# Plasma_Speaker.net
KiCad netlist of a schematic drawn in Altium Designer
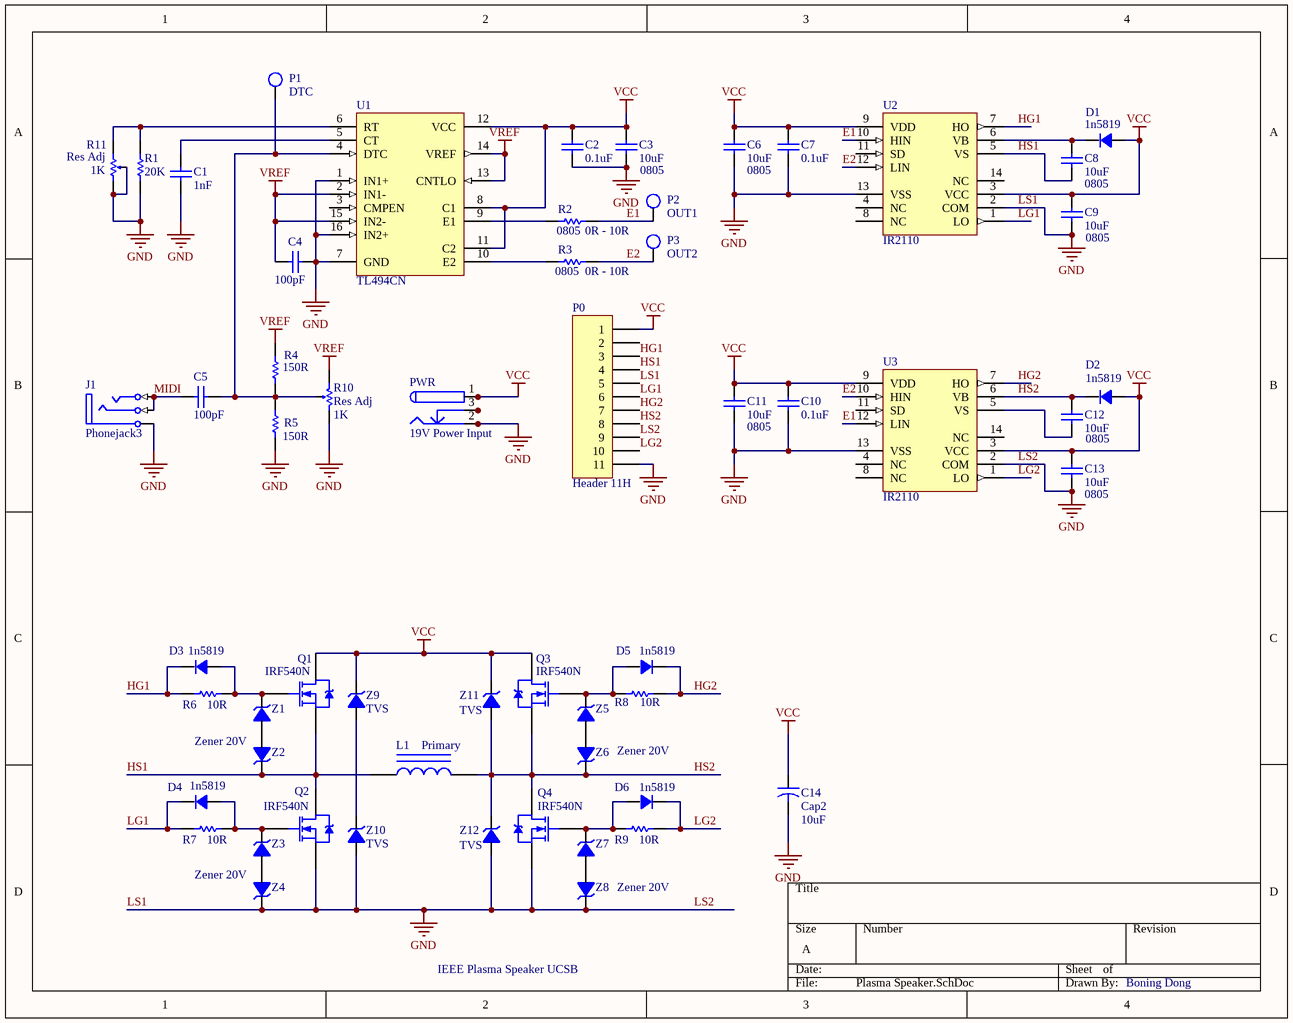
[diagram p0: Plasma Speaker.SchDoc]

(export (version "E")
  (design (tool "Eeschema 10.0.6"))
  (components
    (comp (ref "C1")
      (value "1nF")
      (footprint "RAD-0.3")
      (description "Capacitor")
      (fields (field (name "Comment") "0603") (field (name "PUBLISHER") "Altium Limited"))
      (libsource (lib "Miscellaneous Devices") (part "Cap"))
    )
    (comp (ref "C2")
      (value "0.1uF")
      (footprint "RAD-0.3")
      (description "Capacitor")
      (fields (field (name "Comment") "0603") (field (name "PUBLISHER") "Altium Limited"))
      (libsource (lib "Miscellaneous Devices") (part "Cap"))
    )
    (comp (ref "C3")
      (value "0805")
      (footprint "RAD-0.3")
      (description "Capacitor")
      (fields (field (name "ALTIUM_VALUE") "10uF") (field (name "PUBLISHER") "Altium Limited"))
      (libsource (lib "Miscellaneous Devices") (part "Cap"))
    )
    (comp (ref "C4")
      (value "100pF")
      (footprint "RAD-0.3")
      (description "Capacitor")
      (fields (field (name "Comment") "0603") (field (name "PUBLISHER") "Altium Limited"))
      (libsource (lib "Miscellaneous Devices") (part "Cap"))
    )
    (comp (ref "C5")
      (value "100pF")
      (footprint "RAD-0.3")
      (description "Capacitor")
      (fields (field (name "Comment") "0603") (field (name "PUBLISHER") "Altium Limited"))
      (libsource (lib "Miscellaneous Devices") (part "Cap"))
    )
    (comp (ref "C6")
      (value "0805")
      (footprint "RAD-0.3")
      (description "Capacitor")
      (fields (field (name "ALTIUM_VALUE") "10uF") (field (name "PUBLISHER") "Altium Limited"))
      (libsource (lib "Miscellaneous Devices") (part "Cap"))
    )
    (comp (ref "C7")
      (value "0.1uF")
      (footprint "RAD-0.3")
      (description "Capacitor")
      (fields (field (name "Comment") "0603") (field (name "PUBLISHER") "Altium Limited"))
      (libsource (lib "Miscellaneous Devices") (part "Cap"))
    )
    (comp (ref "C8")
      (value "0805")
      (footprint "RAD-0.3")
      (description "Capacitor")
      (fields (field (name "ALTIUM_VALUE") "10uF") (field (name "PUBLISHER") "Altium Limited"))
      (libsource (lib "Miscellaneous Devices") (part "Cap"))
    )
    (comp (ref "C9")
      (value "0805")
      (footprint "RAD-0.3")
      (description "Capacitor")
      (fields (field (name "ALTIUM_VALUE") "10uF") (field (name "PUBLISHER") "Altium Limited"))
      (libsource (lib "Miscellaneous Devices") (part "Cap"))
    )
    (comp (ref "C10")
      (value "0.1uF")
      (footprint "RAD-0.3")
      (description "Capacitor")
      (fields (field (name "Comment") "0603") (field (name "PUBLISHER") "Altium Limited"))
      (libsource (lib "Miscellaneous Devices") (part "Cap"))
    )
    (comp (ref "C11")
      (value "0805")
      (footprint "RAD-0.3")
      (description "Capacitor")
      (fields (field (name "ALTIUM_VALUE") "10uF") (field (name "PUBLISHER") "Altium Limited"))
      (libsource (lib "Miscellaneous Devices") (part "Cap"))
    )
    (comp (ref "C12")
      (value "0805")
      (footprint "RAD-0.3")
      (description "Capacitor")
      (fields (field (name "ALTIUM_VALUE") "10uF") (field (name "PUBLISHER") "Altium Limited"))
      (libsource (lib "Miscellaneous Devices") (part "Cap"))
    )
    (comp (ref "C13")
      (value "0805")
      (footprint "RAD-0.3")
      (description "Capacitor")
      (fields (field (name "ALTIUM_VALUE") "10uF") (field (name "PUBLISHER") "Altium Limited"))
      (libsource (lib "Miscellaneous Devices") (part "Cap"))
    )
    (comp (ref "C14")
      (value "Cap2")
      (footprint "CAPR5-4X5")
      (description "Capacitor")
      (fields (field (name "ALTIUM_VALUE") "10uF") (field (name "PUBLISHER") "Altium Limited"))
      (libsource (lib "Miscellaneous Devices") (part "Cap2"))
    )
    (comp (ref "D1")
      (value "1n5819")
      (footprint "DIODE-0.7")
      (description "Zener Diode")
      (fields (field (name "PUBLISHER") "Altium Limited"))
      (libsource (lib "Miscellaneous Devices") (part "Diode S"))
    )
    (comp (ref "D2")
      (value "1n5819")
      (footprint "DIODE-0.7")
      (description "Zener Diode")
      (fields (field (name "PUBLISHER") "Altium Limited"))
      (libsource (lib "Miscellaneous Devices") (part "Diode S"))
    )
    (comp (ref "D3")
      (value "1n5819")
      (footprint "DIODE-0.7")
      (description "Zener Diode")
      (fields (field (name "PUBLISHER") "Altium Limited"))
      (libsource (lib "Miscellaneous Devices") (part "Diode S"))
    )
    (comp (ref "D4")
      (value "1n5819")
      (footprint "DIODE-0.7")
      (description "Zener Diode")
      (fields (field (name "PUBLISHER") "Altium Limited"))
      (libsource (lib "Miscellaneous Devices") (part "Diode S"))
    )
    (comp (ref "D5")
      (value "1n5819")
      (footprint "DIODE-0.7")
      (description "Zener Diode")
      (fields (field (name "PUBLISHER") "Altium Limited"))
      (libsource (lib "Miscellaneous Devices") (part "Diode S"))
    )
    (comp (ref "D6")
      (value "1n5819")
      (footprint "DIODE-0.7")
      (description "Zener Diode")
      (fields (field (name "PUBLISHER") "Altium Limited"))
      (libsource (lib "Miscellaneous Devices") (part "Diode S"))
    )
    (comp (ref "J1")
      (value "Phonejack3")
      (footprint "JACK/6-V3")
      (description "Jack Socket, 1/4\" [6.5mm], Thru-Hole, Vertical, 3-Conductor Open Circuit (Non-Normalling)")
      (fields (field (name "PUBLISHER") "Altium Limited"))
      (libsource (lib "Miscellaneous Connectors") (part "Phonejack3"))
    )
    (comp (ref "L1")
      (value "Primary")
      (footprint "AXIAL-0.9")
      (description "Magnetic-Core Inductor")
      (fields (field (name "Comment") "Inductor Iron") (field (name "PUBLISHER") "Altium Limited"))
      (libsource (lib "Miscellaneous Devices") (part "Inductor Iron"))
    )
    (comp (ref "P0")
      (value "Header 11H")
      (footprint "HDR1X11H")
      (description "Header, 11-Pin, Right Angle")
      (fields (field (name "PUBLISHER") "Altium Limited"))
      (libsource (lib "Miscellaneous Connectors") (part "Header 11H"))
    )
    (comp (ref "P1")
      (value "DTC")
      (description "Test Point")
      (libsource (lib "Miscellaneous Connectors") (part "TP"))
    )
    (comp (ref "P2")
      (value "OUT1")
      (description "Test Point")
      (libsource (lib "Miscellaneous Connectors") (part "TP"))
    )
    (comp (ref "P3")
      (value "OUT2")
      (description "Test Point")
      (libsource (lib "Miscellaneous Connectors") (part "TP"))
    )
    (comp (ref "PWR")
      (value "19V Power Input")
      (footprint "KLD-0202")
      (description "Low Voltage Power Supply Connector")
      (fields (field (name "PUBLISHER") "Altium Limited"))
      (libsource (lib "Miscellaneous Connectors") (part "PWR2.5"))
    )
    (comp (ref "Q1")
      (value "IRF540N")
      (footprint "TO-220AB")
      (description "N-Channel Power MOSFET")
      (fields (field (name "PUBLISHER") "Altium Limited"))
      (libsource (lib "Transistor") (part "IRF540N"))
    )
    (comp (ref "Q2")
      (value "IRF540N")
      (footprint "TO-220AB")
      (description "N-Channel Power MOSFET")
      (fields (field (name "PUBLISHER") "Altium Limited"))
      (libsource (lib "Transistor") (part "IRF540N"))
    )
    (comp (ref "Q3")
      (value "IRF540N")
      (footprint "TO-220AB")
      (description "N-Channel Power MOSFET")
      (fields (field (name "PUBLISHER") "Altium Limited"))
      (libsource (lib "Transistor") (part "IRF540N"))
    )
    (comp (ref "Q4")
      (value "IRF540N")
      (footprint "TO-220AB")
      (description "N-Channel Power MOSFET")
      (fields (field (name "PUBLISHER") "Altium Limited"))
      (libsource (lib "Transistor") (part "IRF540N"))
    )
    (comp (ref "R1")
      (value "20K")
      (footprint "AXIAL-0.3")
      (description "Resistor")
      (fields (field (name "Comment") "0603") (field (name "PUBLISHER") "Altium Limited"))
      (libsource (lib "Miscellaneous Devices") (part "Res1"))
    )
    (comp (ref "R2")
      (value "0805")
      (footprint "AXIAL-0.3")
      (description "Resistor")
      (fields (field (name "ALTIUM_VALUE") "0R - 10R") (field (name "PUBLISHER") "Altium Limited"))
      (libsource (lib "Miscellaneous Devices") (part "Res1"))
    )
    (comp (ref "R3")
      (value "0805")
      (footprint "AXIAL-0.3")
      (description "Resistor")
      (fields (field (name "ALTIUM_VALUE") "0R - 10R") (field (name "PUBLISHER") "Altium Limited"))
      (libsource (lib "Miscellaneous Devices") (part "Res1"))
    )
    (comp (ref "R4")
      (value "150R")
      (footprint "AXIAL-0.3")
      (description "Resistor")
      (fields (field (name "Comment") "0603") (field (name "PUBLISHER") "Altium Limited"))
      (libsource (lib "Miscellaneous Devices") (part "Res1"))
    )
    (comp (ref "R5")
      (value "150R")
      (footprint "AXIAL-0.3")
      (description "Resistor")
      (fields (field (name "Comment") "0603") (field (name "PUBLISHER") "Altium Limited"))
      (libsource (lib "Miscellaneous Devices") (part "Res1"))
    )
    (comp (ref "R6")
      (value "10R")
      (footprint "AXIAL-0.3")
      (description "Resistor")
      (fields (field (name "Comment") "0805") (field (name "PUBLISHER") "Altium Limited"))
      (libsource (lib "Miscellaneous Devices") (part "Res1"))
    )
    (comp (ref "R7")
      (value "10R")
      (footprint "AXIAL-0.3")
      (description "Resistor")
      (fields (field (name "Comment") "0805") (field (name "PUBLISHER") "Altium Limited"))
      (libsource (lib "Miscellaneous Devices") (part "Res1"))
    )
    (comp (ref "R8")
      (value "10R")
      (footprint "AXIAL-0.3")
      (description "Resistor")
      (fields (field (name "Comment") "0805") (field (name "PUBLISHER") "Altium Limited"))
      (libsource (lib "Miscellaneous Devices") (part "Res1"))
    )
    (comp (ref "R9")
      (value "10R")
      (footprint "AXIAL-0.3")
      (description "Resistor")
      (fields (field (name "Comment") "0805") (field (name "PUBLISHER") "Altium Limited"))
      (libsource (lib "Miscellaneous Devices") (part "Res1"))
    )
    (comp (ref "R10")
      (value "Res Adj")
      (footprint "AXIAL-0.3")
      (description "Resistor")
      (fields (field (name "ALTIUM_VALUE") "1K") (field (name "PUBLISHER") "Altium Limited"))
      (libsource (lib "Miscellaneous Devices") (part "Res Adj"))
    )
    (comp (ref "R11")
      (value "Res Adj")
      (footprint "AXIAL-0.3")
      (description "Resistor")
      (fields (field (name "ALTIUM_VALUE") "1K") (field (name "PUBLISHER") "Altium Limited"))
      (libsource (lib "Miscellaneous Devices") (part "Res Adj"))
    )
    (comp (ref "U1")
      (value "TL494CN")
      (footprint "648-06")
      (description "Switchmode Pulse Width Modulation Control Circuit")
      (fields (field (name "PUBLISHER") "Altium Limited"))
      (libsource (lib "Motorola Power Mgt SMPS Controller") (part "TL494CN"))
    )
    (comp (ref "U2")
      (value "IR2110")
      (footprint "PDIP14")
      (description "High and Low Side Driver")
      (fields (field (name "PUBLISHER") "Altium Limited"))
      (libsource (lib "IR Interface Bridge Driver") (part "IR2110"))
    )
    (comp (ref "U3")
      (value "IR2110")
      (footprint "PDIP14")
      (description "High and Low Side Driver")
      (fields (field (name "PUBLISHER") "Altium Limited"))
      (libsource (lib "IR Interface Bridge Driver") (part "IR2110"))
    )
    (comp (ref "Z1")
      (value "Zener 20V")
      (footprint "DIODE-0.7")
      (description "Zener Diode")
      (fields (field (name "PUBLISHER") "Altium Limited"))
      (libsource (lib "Miscellaneous Devices") (part "Zener"))
    )
    (comp (ref "Z2")
      (value "Zener")
      (footprint "DIODE-0.7")
      (description "Zener Diode")
      (fields (field (name "PUBLISHER") "Altium Limited"))
      (libsource (lib "Miscellaneous Devices") (part "Zener"))
    )
    (comp (ref "Z3")
      (value "Zener 20V")
      (footprint "DIODE-0.7")
      (description "Zener Diode")
      (fields (field (name "PUBLISHER") "Altium Limited"))
      (libsource (lib "Miscellaneous Devices") (part "Zener"))
    )
    (comp (ref "Z4")
      (value "Zener")
      (footprint "DIODE-0.7")
      (description "Zener Diode")
      (fields (field (name "PUBLISHER") "Altium Limited"))
      (libsource (lib "Miscellaneous Devices") (part "Zener"))
    )
    (comp (ref "Z5")
      (value "Zener 20V")
      (footprint "DIODE-0.7")
      (description "Zener Diode")
      (fields (field (name "PUBLISHER") "Altium Limited"))
      (libsource (lib "Miscellaneous Devices") (part "Zener"))
    )
    (comp (ref "Z6")
      (value "Zener")
      (footprint "DIODE-0.7")
      (description "Zener Diode")
      (fields (field (name "PUBLISHER") "Altium Limited"))
      (libsource (lib "Miscellaneous Devices") (part "Zener"))
    )
    (comp (ref "Z7")
      (value "Zener 20V")
      (footprint "DIODE-0.7")
      (description "Zener Diode")
      (fields (field (name "PUBLISHER") "Altium Limited"))
      (libsource (lib "Miscellaneous Devices") (part "Zener"))
    )
    (comp (ref "Z8")
      (value "Zener")
      (footprint "DIODE-0.7")
      (description "Zener Diode")
      (fields (field (name "PUBLISHER") "Altium Limited"))
      (libsource (lib "Miscellaneous Devices") (part "Zener"))
    )
    (comp (ref "Z9")
      (value "TVS")
      (footprint "DIODE-0.7")
      (description "Zener Diode")
      (fields (field (name "PUBLISHER") "Altium Limited"))
      (libsource (lib "Miscellaneous Devices") (part "Zener"))
    )
    (comp (ref "Z10")
      (value "TVS")
      (footprint "DIODE-0.7")
      (description "Zener Diode")
      (fields (field (name "PUBLISHER") "Altium Limited"))
      (libsource (lib "Miscellaneous Devices") (part "Zener"))
    )
    (comp (ref "Z11")
      (value "TVS")
      (footprint "DIODE-0.7")
      (description "Zener Diode")
      (fields (field (name "PUBLISHER") "Altium Limited"))
      (libsource (lib "Miscellaneous Devices") (part "Zener"))
    )
    (comp (ref "Z12")
      (value "TVS")
      (footprint "DIODE-0.7")
      (description "Zener Diode")
      (fields (field (name "PUBLISHER") "Altium Limited"))
      (libsource (lib "Miscellaneous Devices") (part "Zener"))
    )
  )
  (nets
    (net (code "1") (name "/E1") (class "Default")
      (node (ref "P2") (pin "1") (pinfunction "1_1") (pintype "passive"))
      (node (ref "R2") (pin "1") (pinfunction "1_1") (pintype "passive"))
      (node (ref "U2") (pin "10") (pinfunction "HIN_10") (pintype "input"))
      (node (ref "U3") (pin "12") (pinfunction "LIN_12") (pintype "input"))
    )
    (net (code "2") (name "/E2") (class "Default")
      (node (ref "P3") (pin "1") (pinfunction "1_1") (pintype "passive"))
      (node (ref "R3") (pin "1") (pinfunction "1_1") (pintype "passive"))
      (node (ref "U2") (pin "12") (pinfunction "LIN_12") (pintype "input"))
      (node (ref "U3") (pin "10") (pinfunction "HIN_10") (pintype "input"))
    )
    (net (code "3") (name "/HG1") (class "Default")
      (node (ref "D3") (pin "2") (pinfunction "2_2") (pintype "passive"))
      (node (ref "P0") (pin "3") (pinfunction "3_3") (pintype "passive"))
      (node (ref "R6") (pin "2") (pinfunction "2_2") (pintype "passive"))
      (node (ref "U2") (pin "7") (pinfunction "HO_7") (pintype "output"))
    )
    (net (code "4") (name "/HG2") (class "Default")
      (node (ref "D5") (pin "2") (pinfunction "2_2") (pintype "passive"))
      (node (ref "P0") (pin "7") (pinfunction "7_7") (pintype "passive"))
      (node (ref "R8") (pin "1") (pinfunction "1_1") (pintype "passive"))
      (node (ref "U3") (pin "7") (pinfunction "HO_7") (pintype "output"))
    )
    (net (code "5") (name "/HS1") (class "Default")
      (node (ref "C8") (pin "1") (pinfunction "1_1") (pintype "passive"))
      (node (ref "L1") (pin "1") (pinfunction "1_1") (pintype "passive"))
      (node (ref "P0") (pin "4") (pinfunction "4_4") (pintype "passive"))
      (node (ref "Q1") (pin "3") (pinfunction "S_3") (pintype "passive"))
      (node (ref "Q2") (pin "2") (pinfunction "D_2") (pintype "passive"))
      (node (ref "U2") (pin "5") (pinfunction "VS_5") (pintype "power_in"))
      (node (ref "Z2") (pin "2") (pinfunction "2_2") (pintype "passive"))
    )
    (net (code "6") (name "/HS2") (class "Default")
      (node (ref "C12") (pin "2") (pinfunction "2_2") (pintype "passive"))
      (node (ref "D2") (pin "2") (pinfunction "2_2") (pintype "passive"))
      (node (ref "L1") (pin "2") (pinfunction "2_2") (pintype "passive"))
      (node (ref "P0") (pin "8") (pinfunction "8_8") (pintype "passive"))
      (node (ref "Q3") (pin "3") (pinfunction "S_3") (pintype "passive"))
      (node (ref "Q4") (pin "2") (pinfunction "D_2") (pintype "passive"))
      (node (ref "U3") (pin "6") (pinfunction "VB_6") (pintype "power_in"))
      (node (ref "Z11") (pin "1") (pinfunction "1_1") (pintype "passive"))
      (node (ref "Z12") (pin "2") (pinfunction "2_2") (pintype "passive"))
      (node (ref "Z6") (pin "2") (pinfunction "2_2") (pintype "passive"))
    )
    (net (code "7") (name "/LG1") (class "Default")
      (node (ref "D4") (pin "2") (pinfunction "2_2") (pintype "passive"))
      (node (ref "P0") (pin "6") (pinfunction "6_6") (pintype "passive"))
      (node (ref "R7") (pin "2") (pinfunction "2_2") (pintype "passive"))
      (node (ref "U2") (pin "1") (pinfunction "LO_1") (pintype "output"))
    )
    (net (code "8") (name "/LG2") (class "Default")
      (node (ref "D6") (pin "2") (pinfunction "2_2") (pintype "passive"))
      (node (ref "P0") (pin "10") (pinfunction "10_10") (pintype "passive"))
      (node (ref "R9") (pin "1") (pinfunction "1_1") (pintype "passive"))
      (node (ref "U3") (pin "1") (pinfunction "LO_1") (pintype "output"))
    )
    (net (code "9") (name "/MIDI") (class "Default")
      (node (ref "C5") (pin "1") (pinfunction "1_1") (pintype "passive"))
      (node (ref "J1") (pin "1") (pinfunction "T_1") (pintype "input"))
      (node (ref "J1") (pin "3") (pinfunction "R_3") (pintype "input"))
    )
    (net (code "10") (name "GND") (class "Default")
      (node (ref "C1") (pin "1") (pinfunction "1_1") (pintype "passive"))
      (node (ref "C10") (pin "1") (pinfunction "1_1") (pintype "passive"))
      (node (ref "C11") (pin "1") (pinfunction "1_1") (pintype "passive"))
      (node (ref "C13") (pin "1") (pinfunction "1_1") (pintype "passive"))
      (node (ref "C14") (pin "2") (pinfunction "2_2") (pintype "passive"))
      (node (ref "C2") (pin "1") (pinfunction "1_1") (pintype "passive"))
      (node (ref "C3") (pin "1") (pinfunction "1_1") (pintype "passive"))
      (node (ref "C4") (pin "1") (pinfunction "1_1") (pintype "passive"))
      (node (ref "C6") (pin "1") (pinfunction "1_1") (pintype "passive"))
      (node (ref "C7") (pin "1") (pinfunction "1_1") (pintype "passive"))
      (node (ref "C9") (pin "1") (pinfunction "1_1") (pintype "passive"))
      (node (ref "J1") (pin "5") (pinfunction "S_5") (pintype "power_in"))
      (node (ref "P0") (pin "11") (pinfunction "11_11") (pintype "passive"))
      (node (ref "P0") (pin "5") (pinfunction "5_5") (pintype "passive"))
      (node (ref "P0") (pin "9") (pinfunction "9_9") (pintype "passive"))
      (node (ref "PWR") (pin "2") (pinfunction "2_2") (pintype "power_in"))
      (node (ref "PWR") (pin "2A") (pinfunction "2A_2A") (pintype "power_in"))
      (node (ref "PWR") (pin "2B") (pinfunction "2B_2B") (pintype "power_in"))
      (node (ref "Q2") (pin "3") (pinfunction "S_3") (pintype "passive"))
      (node (ref "Q4") (pin "3") (pinfunction "S_3") (pintype "passive"))
      (node (ref "R1") (pin "1") (pinfunction "1_1") (pintype "passive"))
      (node (ref "R10") (pin "3") (pinfunction "3_3") (pintype "passive"))
      (node (ref "R11") (pin "2") (pinfunction "2_2") (pintype "passive"))
      (node (ref "R11") (pin "3") (pinfunction "3_3") (pintype "passive"))
      (node (ref "R5") (pin "1") (pinfunction "1_1") (pintype "passive"))
      (node (ref "U1") (pin "1") (pinfunction "IN1+_1") (pintype "input"))
      (node (ref "U1") (pin "16") (pinfunction "IN2+_16") (pintype "input"))
      (node (ref "U1") (pin "7") (pinfunction "GND_7") (pintype "power_in"))
      (node (ref "U2") (pin "13") (pinfunction "VSS_13") (pintype "power_in"))
      (node (ref "U2") (pin "2") (pinfunction "COM_2") (pintype "power_in"))
      (node (ref "U3") (pin "13") (pinfunction "VSS_13") (pintype "power_in"))
      (node (ref "U3") (pin "2") (pinfunction "COM_2") (pintype "power_in"))
      (node (ref "Z10") (pin "1") (pinfunction "1_1") (pintype "passive"))
      (node (ref "Z12") (pin "1") (pinfunction "1_1") (pintype "passive"))
      (node (ref "Z4") (pin "2") (pinfunction "2_2") (pintype "passive"))
      (node (ref "Z8") (pin "2") (pinfunction "2_2") (pintype "passive"))
    )
    (net (code "11") (name "Net-(PWR-Pad3)") (class "Default")
      (node (ref "PWR") (pin "3") (pinfunction "3_3") (pintype "power_in"))
      (node (ref "PWR") (pin "3A") (pinfunction "3A_3A") (pintype "power_in"))
      (node (ref "PWR") (pin "3B") (pinfunction "3B_3B") (pintype "power_in"))
    )
    (net (code "12") (name "Net-(Q1-G)") (class "Default")
      (node (ref "D3") (pin "1") (pinfunction "1_1") (pintype "passive"))
      (node (ref "Q1") (pin "1") (pinfunction "G_1") (pintype "passive"))
      (node (ref "R6") (pin "1") (pinfunction "1_1") (pintype "passive"))
      (node (ref "Z1") (pin "2") (pinfunction "2_2") (pintype "passive"))
    )
    (net (code "13") (name "Net-(Q2-G)") (class "Default")
      (node (ref "D4") (pin "1") (pinfunction "1_1") (pintype "passive"))
      (node (ref "Q2") (pin "1") (pinfunction "G_1") (pintype "passive"))
      (node (ref "R7") (pin "1") (pinfunction "1_1") (pintype "passive"))
      (node (ref "Z3") (pin "2") (pinfunction "2_2") (pintype "passive"))
    )
    (net (code "14") (name "Net-(Q3-G)") (class "Default")
      (node (ref "D5") (pin "1") (pinfunction "1_1") (pintype "passive"))
      (node (ref "Q3") (pin "1") (pinfunction "G_1") (pintype "passive"))
      (node (ref "R8") (pin "2") (pinfunction "2_2") (pintype "passive"))
      (node (ref "Z5") (pin "2") (pinfunction "2_2") (pintype "passive"))
    )
    (net (code "15") (name "Net-(Q4-G)") (class "Default")
      (node (ref "D6") (pin "1") (pinfunction "1_1") (pintype "passive"))
      (node (ref "Q4") (pin "1") (pinfunction "G_1") (pintype "passive"))
      (node (ref "R9") (pin "2") (pinfunction "2_2") (pintype "passive"))
      (node (ref "Z7") (pin "2") (pinfunction "2_2") (pintype "passive"))
    )
    (net (code "16") (name "Net-(U1-CT)") (class "Default")
      (node (ref "C1") (pin "2") (pinfunction "2_2") (pintype "passive"))
      (node (ref "U1") (pin "5") (pinfunction "CT_5") (pintype "passive"))
    )
    (net (code "17") (name "Net-(U1-DTC)") (class "Default")
      (node (ref "C5") (pin "2") (pinfunction "2_2") (pintype "passive"))
      (node (ref "P1") (pin "1") (pinfunction "1_1") (pintype "passive"))
      (node (ref "R10") (pin "2") (pinfunction "2_2") (pintype "passive"))
      (node (ref "R4") (pin "1") (pinfunction "1_1") (pintype "passive"))
      (node (ref "R5") (pin "2") (pinfunction "2_2") (pintype "passive"))
      (node (ref "U1") (pin "4") (pinfunction "DTC_4") (pintype "input"))
    )
    (net (code "18") (name "Net-(U1-E1)") (class "Default")
      (node (ref "R2") (pin "2") (pinfunction "2_2") (pintype "passive"))
      (node (ref "U1") (pin "9") (pinfunction "E1_9") (pintype "passive"))
    )
    (net (code "19") (name "Net-(U1-E2)") (class "Default")
      (node (ref "R3") (pin "2") (pinfunction "2_2") (pintype "passive"))
      (node (ref "U1") (pin "10") (pinfunction "E2_10") (pintype "passive"))
    )
    (net (code "20") (name "Net-(U1-RT)") (class "Default")
      (node (ref "R1") (pin "2") (pinfunction "2_2") (pintype "passive"))
      (node (ref "R11") (pin "1") (pinfunction "1_1") (pintype "passive"))
      (node (ref "U1") (pin "6") (pinfunction "RT_6") (pintype "passive"))
    )
    (net (code "21") (name "Net-(U2-VB)") (class "Default")
      (node (ref "C8") (pin "2") (pinfunction "2_2") (pintype "passive"))
      (node (ref "D1") (pin "2") (pinfunction "2_2") (pintype "passive"))
      (node (ref "U2") (pin "6") (pinfunction "VB_6") (pintype "power_in"))
    )
    (net (code "22") (name "Net-(U3-VS)") (class "Default")
      (node (ref "C12") (pin "1") (pinfunction "1_1") (pintype "passive"))
      (node (ref "U3") (pin "5") (pinfunction "VS_5") (pintype "power_in"))
    )
    (net (code "23") (name "Net-(Z1-Pad1)") (class "Default")
      (node (ref "Z1") (pin "1") (pinfunction "1_1") (pintype "passive"))
      (node (ref "Z2") (pin "1") (pinfunction "1_1") (pintype "passive"))
    )
    (net (code "24") (name "Net-(Z3-Pad1)") (class "Default")
      (node (ref "Z3") (pin "1") (pinfunction "1_1") (pintype "passive"))
      (node (ref "Z4") (pin "1") (pinfunction "1_1") (pintype "passive"))
    )
    (net (code "25") (name "Net-(Z5-Pad1)") (class "Default")
      (node (ref "Z5") (pin "1") (pinfunction "1_1") (pintype "passive"))
      (node (ref "Z6") (pin "1") (pinfunction "1_1") (pintype "passive"))
    )
    (net (code "26") (name "Net-(Z7-Pad1)") (class "Default")
      (node (ref "Z7") (pin "1") (pinfunction "1_1") (pintype "passive"))
      (node (ref "Z8") (pin "1") (pinfunction "1_1") (pintype "passive"))
    )
    (net (code "27") (name "Net-(Z10-Pad2)") (class "Default")
      (node (ref "Z10") (pin "2") (pinfunction "2_2") (pintype "passive"))
      (node (ref "Z9") (pin "1") (pinfunction "1_1") (pintype "passive"))
    )
    (net (code "28") (name "VCC") (class "Default")
      (node (ref "C10") (pin "2") (pinfunction "2_2") (pintype "passive"))
      (node (ref "C11") (pin "2") (pinfunction "2_2") (pintype "passive"))
      (node (ref "C13") (pin "2") (pinfunction "2_2") (pintype "passive"))
      (node (ref "C14") (pin "1") (pinfunction "1_1") (pintype "passive"))
      (node (ref "C2") (pin "2") (pinfunction "2_2") (pintype "passive"))
      (node (ref "C3") (pin "2") (pinfunction "2_2") (pintype "passive"))
      (node (ref "C6") (pin "2") (pinfunction "2_2") (pintype "passive"))
      (node (ref "C7") (pin "2") (pinfunction "2_2") (pintype "passive"))
      (node (ref "C9") (pin "2") (pinfunction "2_2") (pintype "passive"))
      (node (ref "D1") (pin "1") (pinfunction "1_1") (pintype "passive"))
      (node (ref "D2") (pin "1") (pinfunction "1_1") (pintype "passive"))
      (node (ref "P0") (pin "1") (pinfunction "1_1") (pintype "passive"))
      (node (ref "PWR") (pin "1") (pinfunction "1_1") (pintype "power_in"))
      (node (ref "PWR") (pin "1A") (pinfunction "1A_1A") (pintype "power_in"))
      (node (ref "PWR") (pin "1B") (pinfunction "1B_1B") (pintype "power_in"))
      (node (ref "Q1") (pin "2") (pinfunction "D_2") (pintype "passive"))
      (node (ref "Q3") (pin "2") (pinfunction "D_2") (pintype "passive"))
      (node (ref "U1") (pin "11") (pinfunction "C2_11") (pintype "passive"))
      (node (ref "U1") (pin "12") (pinfunction "VCC_12") (pintype "power_in"))
      (node (ref "U1") (pin "8") (pinfunction "C1_8") (pintype "passive"))
      (node (ref "U2") (pin "3") (pinfunction "VCC_3") (pintype "power_in"))
      (node (ref "U2") (pin "9") (pinfunction "VDD_9") (pintype "power_in"))
      (node (ref "U3") (pin "3") (pinfunction "VCC_3") (pintype "power_in"))
      (node (ref "U3") (pin "9") (pinfunction "VDD_9") (pintype "power_in"))
      (node (ref "Z11") (pin "2") (pinfunction "2_2") (pintype "passive"))
      (node (ref "Z9") (pin "2") (pinfunction "2_2") (pintype "passive"))
    )
    (net (code "29") (name "VREF") (class "Default")
      (node (ref "C4") (pin "2") (pinfunction "2_2") (pintype "passive"))
      (node (ref "R10") (pin "1") (pinfunction "1_1") (pintype "passive"))
      (node (ref "R4") (pin "2") (pinfunction "2_2") (pintype "passive"))
      (node (ref "U1") (pin "13") (pinfunction "CNTLO_13") (pintype "input"))
      (node (ref "U1") (pin "14") (pinfunction "VREF_14") (pintype "output"))
      (node (ref "U1") (pin "15") (pinfunction "IN2-_15") (pintype "input"))
      (node (ref "U1") (pin "2") (pinfunction "IN1-_2") (pintype "input"))
    )
    (net (code "30") (name "unconnected-(P0-Pad2)") (class "Default")
      (node (ref "P0") (pin "2") (pinfunction "2_2") (pintype "passive"))
    )
    (net (code "31") (name "unconnected-(U1-CMPEN-Pad3)") (class "Default")
      (node (ref "U1") (pin "3") (pinfunction "CMPEN_3") (pintype "input"))
    )
    (net (code "32") (name "unconnected-(U2-NC-Pad4)") (class "Default")
      (node (ref "U2") (pin "4") (pinfunction "NC_4") (pintype "passive"))
    )
    (net (code "33") (name "unconnected-(U2-NC-Pad8)") (class "Default")
      (node (ref "U2") (pin "8") (pinfunction "NC_8") (pintype "passive"))
    )
    (net (code "34") (name "unconnected-(U2-NC-Pad14)") (class "Default")
      (node (ref "U2") (pin "14") (pinfunction "NC_14") (pintype "passive"))
    )
    (net (code "35") (name "unconnected-(U2-SD-Pad11)") (class "Default")
      (node (ref "U2") (pin "11") (pinfunction "SD_11") (pintype "input"))
    )
    (net (code "36") (name "unconnected-(U3-NC-Pad4)") (class "Default")
      (node (ref "U3") (pin "4") (pinfunction "NC_4") (pintype "passive"))
    )
    (net (code "37") (name "unconnected-(U3-NC-Pad8)") (class "Default")
      (node (ref "U3") (pin "8") (pinfunction "NC_8") (pintype "passive"))
    )
    (net (code "38") (name "unconnected-(U3-NC-Pad14)") (class "Default")
      (node (ref "U3") (pin "14") (pinfunction "NC_14") (pintype "passive"))
    )
    (net (code "39") (name "unconnected-(U3-SD-Pad11)") (class "Default")
      (node (ref "U3") (pin "11") (pinfunction "SD_11") (pintype "input"))
    )
  )
)
